# edition_2_-1.net
KiCad netlist of a schematic drawn in EAGLE
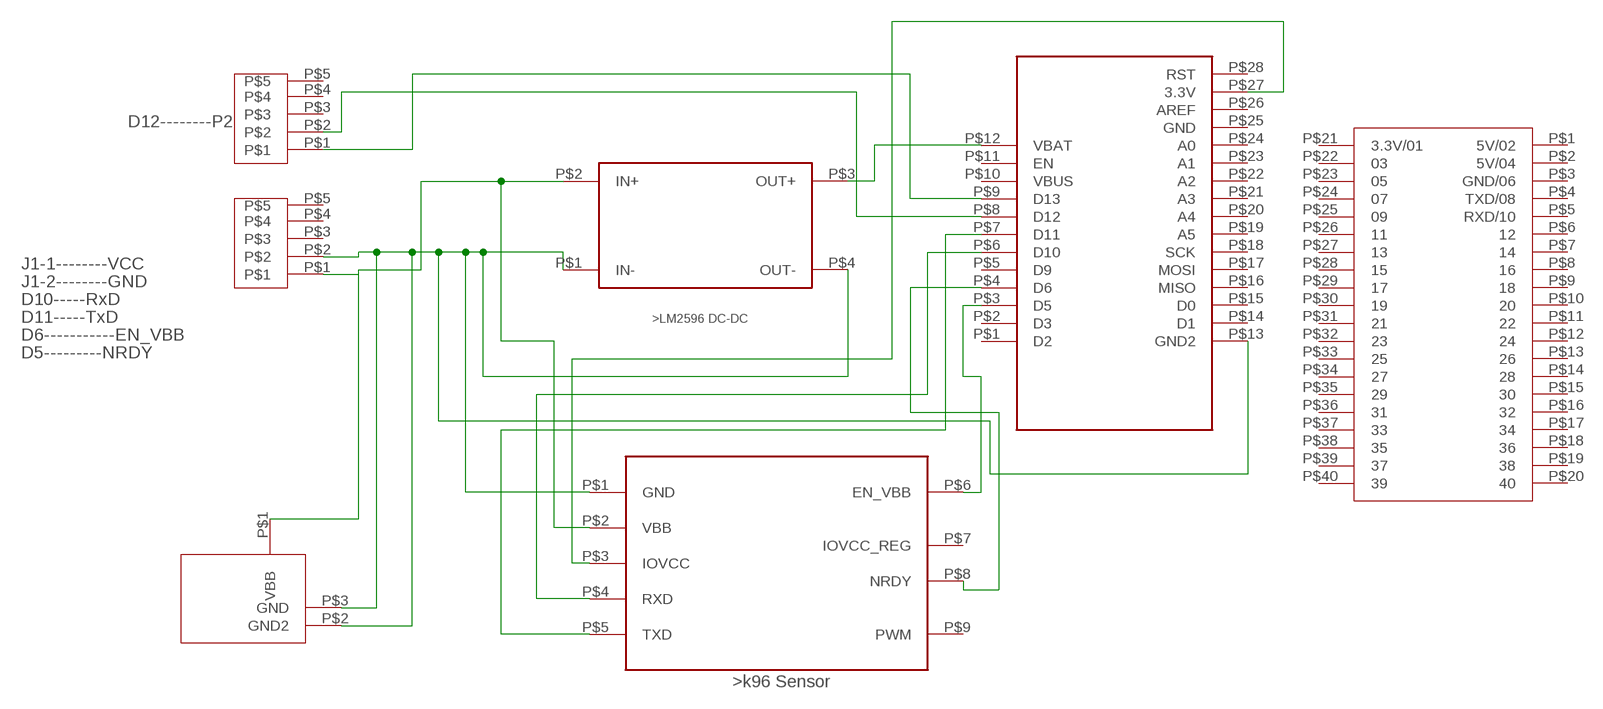
[diagram p0: schematic, sheet 1]

(export (version "E")
  (design (tool "Eeschema 10.0.6"))
  (components
    (comp (ref "DCDC1")
      (value "DCDC")
      (footprint "eagle-import:DCDC")
      (libsource (lib "eagle-import") (part "DCDC"))
    )
    (comp (ref "FEATHER1")
      (value "FEATHER")
      (footprint "eagle-import:FEATHER")
      (libsource (lib "eagle-import") (part "FEATHER"))
    )
    (comp (ref "K96SENSOR1")
      (value "K96SENSOR")
      (footprint "eagle-import:K96SENSOR")
      (libsource (lib "eagle-import") (part "K96SENSOR"))
    )
    (comp (ref "PIN1")
      (value "PIN")
      (footprint "eagle-import:PIN")
      (libsource (lib "eagle-import") (part "PIN"))
    )
    (comp (ref "PIN2")
      (value "PIN")
      (footprint "eagle-import:PIN")
      (libsource (lib "eagle-import") (part "PIN"))
    )
    (comp (ref "U$1")
      (value "POWER")
      (footprint "eagle-import:POWERIN")
      (libsource (lib "eagle-import") (part "POWER"))
    )
    (comp (ref "U$2")
      (value "RASPBERRYPI")
      (footprint "eagle-import:RASPBERRYPI")
      (libsource (lib "eagle-import") (part "RASPBERRYPI"))
    )
  )
  (nets
    (net (code "1") (name "Net-(DCDC1-IN+)") (class "Default")
      (node (ref "DCDC1") (pin "P$2") (pinfunction "IN+_P$2") (pintype "bidirectional"))
      (node (ref "K96SENSOR1") (pin "P$2") (pinfunction "VBB_P$2") (pintype "bidirectional"))
      (node (ref "PIN1") (pin "P$1") (pinfunction "P$1_P$1") (pintype "bidirectional"))
      (node (ref "U$1") (pin "P$1") (pinfunction "VBB_P$1") (pintype "bidirectional"))
    )
    (net (code "2") (name "Net-(DCDC1-IN-)") (class "Default")
      (node (ref "DCDC1") (pin "P$1") (pinfunction "IN-_P$1") (pintype "bidirectional"))
      (node (ref "DCDC1") (pin "P$4") (pinfunction "OUT-_P$4") (pintype "bidirectional"))
      (node (ref "FEATHER1") (pin "P$13") (pinfunction "GND2_P$13") (pintype "bidirectional"))
      (node (ref "K96SENSOR1") (pin "P$1") (pinfunction "GND_P$1") (pintype "bidirectional"))
      (node (ref "PIN1") (pin "P$2") (pinfunction "P$2_P$2") (pintype "bidirectional"))
      (node (ref "U$1") (pin "P$2") (pinfunction "GND2_P$2") (pintype "bidirectional"))
      (node (ref "U$1") (pin "P$3") (pinfunction "GND_P$3") (pintype "bidirectional"))
    )
    (net (code "3") (name "Net-(DCDC1-OUT+)") (class "Default")
      (node (ref "DCDC1") (pin "P$3") (pinfunction "OUT+_P$3") (pintype "bidirectional"))
      (node (ref "FEATHER1") (pin "P$12") (pinfunction "VBAT_P$12") (pintype "bidirectional"))
    )
    (net (code "4") (name "Net-(FEATHER1-3.3V)") (class "Default")
      (node (ref "FEATHER1") (pin "P$27") (pinfunction "3.3V_P$27") (pintype "bidirectional"))
      (node (ref "K96SENSOR1") (pin "P$3") (pinfunction "IOVCC_P$3") (pintype "bidirectional"))
    )
    (net (code "5") (name "Net-(FEATHER1-D5)") (class "Default")
      (node (ref "FEATHER1") (pin "P$3") (pinfunction "D5_P$3") (pintype "bidirectional"))
      (node (ref "K96SENSOR1") (pin "P$6") (pinfunction "EN_VBB_P$6") (pintype "bidirectional"))
    )
    (net (code "6") (name "Net-(FEATHER1-D6)") (class "Default")
      (node (ref "FEATHER1") (pin "P$4") (pinfunction "D6_P$4") (pintype "bidirectional"))
      (node (ref "K96SENSOR1") (pin "P$8") (pinfunction "NRDY_P$8") (pintype "bidirectional"))
    )
    (net (code "7") (name "Net-(FEATHER1-D10)") (class "Default")
      (node (ref "FEATHER1") (pin "P$6") (pinfunction "D10_P$6") (pintype "bidirectional"))
      (node (ref "K96SENSOR1") (pin "P$4") (pinfunction "RXD_P$4") (pintype "bidirectional"))
    )
    (net (code "8") (name "Net-(FEATHER1-D11)") (class "Default")
      (node (ref "FEATHER1") (pin "P$7") (pinfunction "D11_P$7") (pintype "bidirectional"))
      (node (ref "K96SENSOR1") (pin "P$5") (pinfunction "TXD_P$5") (pintype "bidirectional"))
    )
    (net (code "9") (name "Net-(FEATHER1-D12)") (class "Default")
      (node (ref "FEATHER1") (pin "P$8") (pinfunction "D12_P$8") (pintype "bidirectional"))
      (node (ref "PIN2") (pin "P$2") (pinfunction "P$2_P$2") (pintype "bidirectional"))
    )
    (net (code "10") (name "Net-(FEATHER1-D13)") (class "Default")
      (node (ref "FEATHER1") (pin "P$9") (pinfunction "D13_P$9") (pintype "bidirectional"))
      (node (ref "PIN2") (pin "P$1") (pinfunction "P$1_P$1") (pintype "bidirectional"))
    )
    (net (code "11") (name "unconnected-(FEATHER1-A0-PadP$24)") (class "Default")
      (node (ref "FEATHER1") (pin "P$24") (pinfunction "A0_P$24") (pintype "bidirectional"))
    )
    (net (code "12") (name "unconnected-(FEATHER1-A1-PadP$23)") (class "Default")
      (node (ref "FEATHER1") (pin "P$23") (pinfunction "A1_P$23") (pintype "bidirectional"))
    )
    (net (code "13") (name "unconnected-(FEATHER1-A2-PadP$22)") (class "Default")
      (node (ref "FEATHER1") (pin "P$22") (pinfunction "A2_P$22") (pintype "bidirectional"))
    )
    (net (code "14") (name "unconnected-(FEATHER1-A3-PadP$21)") (class "Default")
      (node (ref "FEATHER1") (pin "P$21") (pinfunction "A3_P$21") (pintype "bidirectional"))
    )
    (net (code "15") (name "unconnected-(FEATHER1-A4-PadP$20)") (class "Default")
      (node (ref "FEATHER1") (pin "P$20") (pinfunction "A4_P$20") (pintype "bidirectional"))
    )
    (net (code "16") (name "unconnected-(FEATHER1-A5-PadP$19)") (class "Default")
      (node (ref "FEATHER1") (pin "P$19") (pinfunction "A5_P$19") (pintype "bidirectional"))
    )
    (net (code "17") (name "unconnected-(FEATHER1-AREF-PadP$26)") (class "Default")
      (node (ref "FEATHER1") (pin "P$26") (pinfunction "AREF_P$26") (pintype "bidirectional"))
    )
    (net (code "18") (name "unconnected-(FEATHER1-D0-PadP$15)") (class "Default")
      (node (ref "FEATHER1") (pin "P$15") (pinfunction "D0_P$15") (pintype "bidirectional"))
    )
    (net (code "19") (name "unconnected-(FEATHER1-D1-PadP$14)") (class "Default")
      (node (ref "FEATHER1") (pin "P$14") (pinfunction "D1_P$14") (pintype "bidirectional"))
    )
    (net (code "20") (name "unconnected-(FEATHER1-D2-PadP$1)") (class "Default")
      (node (ref "FEATHER1") (pin "P$1") (pinfunction "D2_P$1") (pintype "bidirectional"))
    )
    (net (code "21") (name "unconnected-(FEATHER1-D3-PadP$2)") (class "Default")
      (node (ref "FEATHER1") (pin "P$2") (pinfunction "D3_P$2") (pintype "bidirectional"))
    )
    (net (code "22") (name "unconnected-(FEATHER1-D9-PadP$5)") (class "Default")
      (node (ref "FEATHER1") (pin "P$5") (pinfunction "D9_P$5") (pintype "bidirectional"))
    )
    (net (code "23") (name "unconnected-(FEATHER1-EN-PadP$11)") (class "Default")
      (node (ref "FEATHER1") (pin "P$11") (pinfunction "EN_P$11") (pintype "bidirectional"))
    )
    (net (code "24") (name "unconnected-(FEATHER1-GND-PadP$25)") (class "Default")
      (node (ref "FEATHER1") (pin "P$25") (pinfunction "GND_P$25") (pintype "bidirectional"))
    )
    (net (code "25") (name "unconnected-(FEATHER1-MISO-PadP$16)") (class "Default")
      (node (ref "FEATHER1") (pin "P$16") (pinfunction "MISO_P$16") (pintype "bidirectional"))
    )
    (net (code "26") (name "unconnected-(FEATHER1-MOSI-PadP$17)") (class "Default")
      (node (ref "FEATHER1") (pin "P$17") (pinfunction "MOSI_P$17") (pintype "bidirectional"))
    )
    (net (code "27") (name "unconnected-(FEATHER1-RST-PadP$28)") (class "Default")
      (node (ref "FEATHER1") (pin "P$28") (pinfunction "RST_P$28") (pintype "bidirectional"))
    )
    (net (code "28") (name "unconnected-(FEATHER1-SCK-PadP$18)") (class "Default")
      (node (ref "FEATHER1") (pin "P$18") (pinfunction "SCK_P$18") (pintype "bidirectional"))
    )
    (net (code "29") (name "unconnected-(FEATHER1-VBUS-PadP$10)") (class "Default")
      (node (ref "FEATHER1") (pin "P$10") (pinfunction "VBUS_P$10") (pintype "bidirectional"))
    )
    (net (code "30") (name "unconnected-(K96SENSOR1-IOVCC_REG-PadP$7)") (class "Default")
      (node (ref "K96SENSOR1") (pin "P$7") (pinfunction "IOVCC_REG_P$7") (pintype "bidirectional"))
    )
    (net (code "31") (name "unconnected-(K96SENSOR1-PWM-PadP$9)") (class "Default")
      (node (ref "K96SENSOR1") (pin "P$9") (pinfunction "PWM_P$9") (pintype "bidirectional"))
    )
    (net (code "32") (name "unconnected-(PIN1-PadP$3)") (class "Default")
      (node (ref "PIN1") (pin "P$3") (pinfunction "P$3_P$3") (pintype "bidirectional"))
    )
    (net (code "33") (name "unconnected-(PIN1-PadP$4)") (class "Default")
      (node (ref "PIN1") (pin "P$4") (pinfunction "P$4_P$4") (pintype "bidirectional"))
    )
    (net (code "34") (name "unconnected-(PIN1-PadP$5)") (class "Default")
      (node (ref "PIN1") (pin "P$5") (pinfunction "P$5_P$5") (pintype "bidirectional"))
    )
    (net (code "35") (name "unconnected-(PIN2-PadP$3)") (class "Default")
      (node (ref "PIN2") (pin "P$3") (pinfunction "P$3_P$3") (pintype "bidirectional"))
    )
    (net (code "36") (name "unconnected-(PIN2-PadP$4)") (class "Default")
      (node (ref "PIN2") (pin "P$4") (pinfunction "P$4_P$4") (pintype "bidirectional"))
    )
    (net (code "37") (name "unconnected-(PIN2-PadP$5)") (class "Default")
      (node (ref "PIN2") (pin "P$5") (pinfunction "P$5_P$5") (pintype "bidirectional"))
    )
    (net (code "38") (name "unconnected-(U$2-03-PadP$22)") (class "Default")
      (node (ref "U$2") (pin "P$22") (pinfunction "03_P$22") (pintype "bidirectional"))
    )
    (net (code "39") (name "unconnected-(U$2-3.3V{slash}01-PadP$21)") (class "Default")
      (node (ref "U$2") (pin "P$21") (pinfunction "3.3V/01_P$21") (pintype "bidirectional"))
    )
    (net (code "40") (name "unconnected-(U$2-05-PadP$23)") (class "Default")
      (node (ref "U$2") (pin "P$23") (pinfunction "05_P$23") (pintype "bidirectional"))
    )
    (net (code "41") (name "unconnected-(U$2-5V{slash}02-PadP$1)") (class "Default")
      (node (ref "U$2") (pin "P$1") (pinfunction "5V/02_P$1") (pintype "bidirectional"))
    )
    (net (code "42") (name "unconnected-(U$2-5V{slash}04-PadP$2)") (class "Default")
      (node (ref "U$2") (pin "P$2") (pinfunction "5V/04_P$2") (pintype "bidirectional"))
    )
    (net (code "43") (name "unconnected-(U$2-07-PadP$24)") (class "Default")
      (node (ref "U$2") (pin "P$24") (pinfunction "07_P$24") (pintype "bidirectional"))
    )
    (net (code "44") (name "unconnected-(U$2-09-PadP$25)") (class "Default")
      (node (ref "U$2") (pin "P$25") (pinfunction "09_P$25") (pintype "bidirectional"))
    )
    (net (code "45") (name "unconnected-(U$2-11-PadP$26)") (class "Default")
      (node (ref "U$2") (pin "P$26") (pinfunction "11_P$26") (pintype "bidirectional"))
    )
    (net (code "46") (name "unconnected-(U$2-12-PadP$6)") (class "Default")
      (node (ref "U$2") (pin "P$6") (pinfunction "12_P$6") (pintype "bidirectional"))
    )
    (net (code "47") (name "unconnected-(U$2-13-PadP$27)") (class "Default")
      (node (ref "U$2") (pin "P$27") (pinfunction "13_P$27") (pintype "bidirectional"))
    )
    (net (code "48") (name "unconnected-(U$2-14-PadP$7)") (class "Default")
      (node (ref "U$2") (pin "P$7") (pinfunction "14_P$7") (pintype "bidirectional"))
    )
    (net (code "49") (name "unconnected-(U$2-15-PadP$28)") (class "Default")
      (node (ref "U$2") (pin "P$28") (pinfunction "15_P$28") (pintype "bidirectional"))
    )
    (net (code "50") (name "unconnected-(U$2-16-PadP$8)") (class "Default")
      (node (ref "U$2") (pin "P$8") (pinfunction "16_P$8") (pintype "bidirectional"))
    )
    (net (code "51") (name "unconnected-(U$2-17-PadP$29)") (class "Default")
      (node (ref "U$2") (pin "P$29") (pinfunction "17_P$29") (pintype "bidirectional"))
    )
    (net (code "52") (name "unconnected-(U$2-18-PadP$9)") (class "Default")
      (node (ref "U$2") (pin "P$9") (pinfunction "18_P$9") (pintype "bidirectional"))
    )
    (net (code "53") (name "unconnected-(U$2-19-PadP$30)") (class "Default")
      (node (ref "U$2") (pin "P$30") (pinfunction "19_P$30") (pintype "bidirectional"))
    )
    (net (code "54") (name "unconnected-(U$2-20-PadP$10)") (class "Default")
      (node (ref "U$2") (pin "P$10") (pinfunction "20_P$10") (pintype "bidirectional"))
    )
    (net (code "55") (name "unconnected-(U$2-21-PadP$31)") (class "Default")
      (node (ref "U$2") (pin "P$31") (pinfunction "21_P$31") (pintype "bidirectional"))
    )
    (net (code "56") (name "unconnected-(U$2-22-PadP$11)") (class "Default")
      (node (ref "U$2") (pin "P$11") (pinfunction "22_P$11") (pintype "bidirectional"))
    )
    (net (code "57") (name "unconnected-(U$2-23-PadP$32)") (class "Default")
      (node (ref "U$2") (pin "P$32") (pinfunction "23_P$32") (pintype "bidirectional"))
    )
    (net (code "58") (name "unconnected-(U$2-24-PadP$12)") (class "Default")
      (node (ref "U$2") (pin "P$12") (pinfunction "24_P$12") (pintype "bidirectional"))
    )
    (net (code "59") (name "unconnected-(U$2-25-PadP$33)") (class "Default")
      (node (ref "U$2") (pin "P$33") (pinfunction "25_P$33") (pintype "bidirectional"))
    )
    (net (code "60") (name "unconnected-(U$2-26-PadP$13)") (class "Default")
      (node (ref "U$2") (pin "P$13") (pinfunction "26_P$13") (pintype "bidirectional"))
    )
    (net (code "61") (name "unconnected-(U$2-27-PadP$34)") (class "Default")
      (node (ref "U$2") (pin "P$34") (pinfunction "27_P$34") (pintype "bidirectional"))
    )
    (net (code "62") (name "unconnected-(U$2-28-PadP$14)") (class "Default")
      (node (ref "U$2") (pin "P$14") (pinfunction "28_P$14") (pintype "bidirectional"))
    )
    (net (code "63") (name "unconnected-(U$2-29-PadP$35)") (class "Default")
      (node (ref "U$2") (pin "P$35") (pinfunction "29_P$35") (pintype "bidirectional"))
    )
    (net (code "64") (name "unconnected-(U$2-30-PadP$15)") (class "Default")
      (node (ref "U$2") (pin "P$15") (pinfunction "30_P$15") (pintype "bidirectional"))
    )
    (net (code "65") (name "unconnected-(U$2-31-PadP$36)") (class "Default")
      (node (ref "U$2") (pin "P$36") (pinfunction "31_P$36") (pintype "bidirectional"))
    )
    (net (code "66") (name "unconnected-(U$2-32-PadP$16)") (class "Default")
      (node (ref "U$2") (pin "P$16") (pinfunction "32_P$16") (pintype "bidirectional"))
    )
    (net (code "67") (name "unconnected-(U$2-33-PadP$37)") (class "Default")
      (node (ref "U$2") (pin "P$37") (pinfunction "33_P$37") (pintype "bidirectional"))
    )
    (net (code "68") (name "unconnected-(U$2-34-PadP$17)") (class "Default")
      (node (ref "U$2") (pin "P$17") (pinfunction "34_P$17") (pintype "bidirectional"))
    )
    (net (code "69") (name "unconnected-(U$2-35-PadP$38)") (class "Default")
      (node (ref "U$2") (pin "P$38") (pinfunction "35_P$38") (pintype "bidirectional"))
    )
    (net (code "70") (name "unconnected-(U$2-36-PadP$18)") (class "Default")
      (node (ref "U$2") (pin "P$18") (pinfunction "36_P$18") (pintype "bidirectional"))
    )
    (net (code "71") (name "unconnected-(U$2-37-PadP$39)") (class "Default")
      (node (ref "U$2") (pin "P$39") (pinfunction "37_P$39") (pintype "bidirectional"))
    )
    (net (code "72") (name "unconnected-(U$2-38-PadP$19)") (class "Default")
      (node (ref "U$2") (pin "P$19") (pinfunction "38_P$19") (pintype "bidirectional"))
    )
    (net (code "73") (name "unconnected-(U$2-39-PadP$40)") (class "Default")
      (node (ref "U$2") (pin "P$40") (pinfunction "39_P$40") (pintype "bidirectional"))
    )
    (net (code "74") (name "unconnected-(U$2-40-PadP$20)") (class "Default")
      (node (ref "U$2") (pin "P$20") (pinfunction "40_P$20") (pintype "bidirectional"))
    )
    (net (code "75") (name "unconnected-(U$2-GND{slash}06-PadP$3)") (class "Default")
      (node (ref "U$2") (pin "P$3") (pinfunction "GND/06_P$3") (pintype "bidirectional"))
    )
    (net (code "76") (name "unconnected-(U$2-RXD{slash}10-PadP$5)") (class "Default")
      (node (ref "U$2") (pin "P$5") (pinfunction "RXD/10_P$5") (pintype "bidirectional"))
    )
    (net (code "77") (name "unconnected-(U$2-TXD{slash}08-PadP$4)") (class "Default")
      (node (ref "U$2") (pin "P$4") (pinfunction "TXD/08_P$4") (pintype "bidirectional"))
    )
  )
)
